# Power_Input.net
KiCad netlist of a schematic drawn in Altium Designer
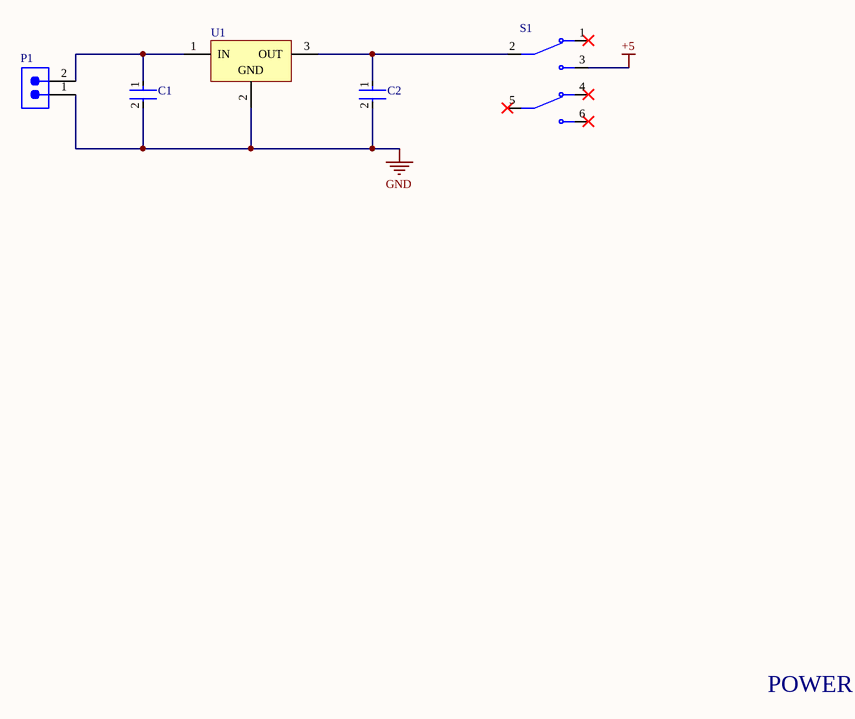
[diagram p0: Power_Input.SchDoc]

(export (version "E")
  (design (tool "Eeschema 10.0.6"))
  (components
    (comp (ref "C1")
      (value "D222K33Y5PL6UJ5R")
      (footprint "FP-D222K33Y5PL6UJ5R-MFG")
      (description "CAP CER 2200PF 500V Y5P RADIAL")
      (fields (field (name "TOLERANCE") "10%"))
      (libsource (lib "Altium Content Vault") (part "02cd4be3c70576c341d710602a673aa"))
    )
    (comp (ref "C2")
      (value "D222K33Y5PL6UJ5R")
      (footprint "FP-D222K33Y5PL6UJ5R-MFG")
      (description "CAP CER 2200PF 500V Y5P RADIAL")
      (fields (field (name "TOLERANCE") "10%"))
      (libsource (lib "Altium Content Vault") (part "02cd4be3c70576c341d710602a673aa"))
    )
    (comp (ref "P1")
      (value "691311500002")
      (footprint "691311500002")
      (fields (field (name "VOLTAGE") "300V"))
      (libsource (lib "Altium Content Vault") (part "TBL - 1R - 02P - Male"))
    )
    (comp (ref "S1")
      (value "TL2230OAF140")
      (footprint "SW_TL2230OAF140")
      (description "Pushbutton Switch DPDT Standard Through Hole")
      (fields (field (name "MF") "E-Switch"))
      (libsource (lib "TL2230OAF140") (part "TL2230OAF140"))
    )
    (comp (ref "U1")
      (value "L7805CP")
      (footprint "TO220FP")
      (description "Positive Voltage Regulator, 5V, 3-Pin TO-220FP")
      (libsource (lib "Altium Content Vault") (part "PM-REG-L4940-SIL3"))
    )
  )
  (nets
    (net (code "1") (name "+5") (class "Default")
      (node (ref "S1") (pin "3") (pinfunction "NO1_3") (pintype "passive"))
    )
    (net (code "2") (name "GND") (class "Default")
      (node (ref "C1") (pin "2") (pinfunction "2_2") (pintype "passive"))
      (node (ref "C2") (pin "2") (pinfunction "2_2") (pintype "passive"))
      (node (ref "P1") (pin "1") (pinfunction "1_1") (pintype "passive"))
      (node (ref "U1") (pin "2") (pinfunction "GND_2") (pintype "power_in"))
    )
    (net (code "3") (name "Net-(S1-COM1)") (class "Default")
      (node (ref "C2") (pin "1") (pinfunction "1_1") (pintype "passive"))
      (node (ref "S1") (pin "2") (pinfunction "COM1_2") (pintype "passive"))
      (node (ref "U1") (pin "3") (pinfunction "OUT_3") (pintype "power_in"))
    )
    (net (code "4") (name "Net-(U1-IN)") (class "Default")
      (node (ref "C1") (pin "1") (pinfunction "1_1") (pintype "passive"))
      (node (ref "P1") (pin "2") (pinfunction "2_2") (pintype "passive"))
      (node (ref "U1") (pin "1") (pinfunction "IN_1") (pintype "power_in"))
    )
    (net (code "5") (name "unconnected-(S1-COM2-Pad5)") (class "Default")
      (node (ref "S1") (pin "5") (pinfunction "COM2_5") (pintype "passive+no_connect"))
    )
    (net (code "6") (name "unconnected-(S1-NC1-Pad1)") (class "Default")
      (node (ref "S1") (pin "1") (pinfunction "NC1_1") (pintype "passive+no_connect"))
    )
    (net (code "7") (name "unconnected-(S1-NC2-Pad4)") (class "Default")
      (node (ref "S1") (pin "4") (pinfunction "NC2_4") (pintype "passive+no_connect"))
    )
    (net (code "8") (name "unconnected-(S1-NO2-Pad6)") (class "Default")
      (node (ref "S1") (pin "6") (pinfunction "NO2_6") (pintype "passive+no_connect"))
    )
  )
)
